# LED_TwoBars.net
KiCad netlist of a schematic drawn in Altium Designer
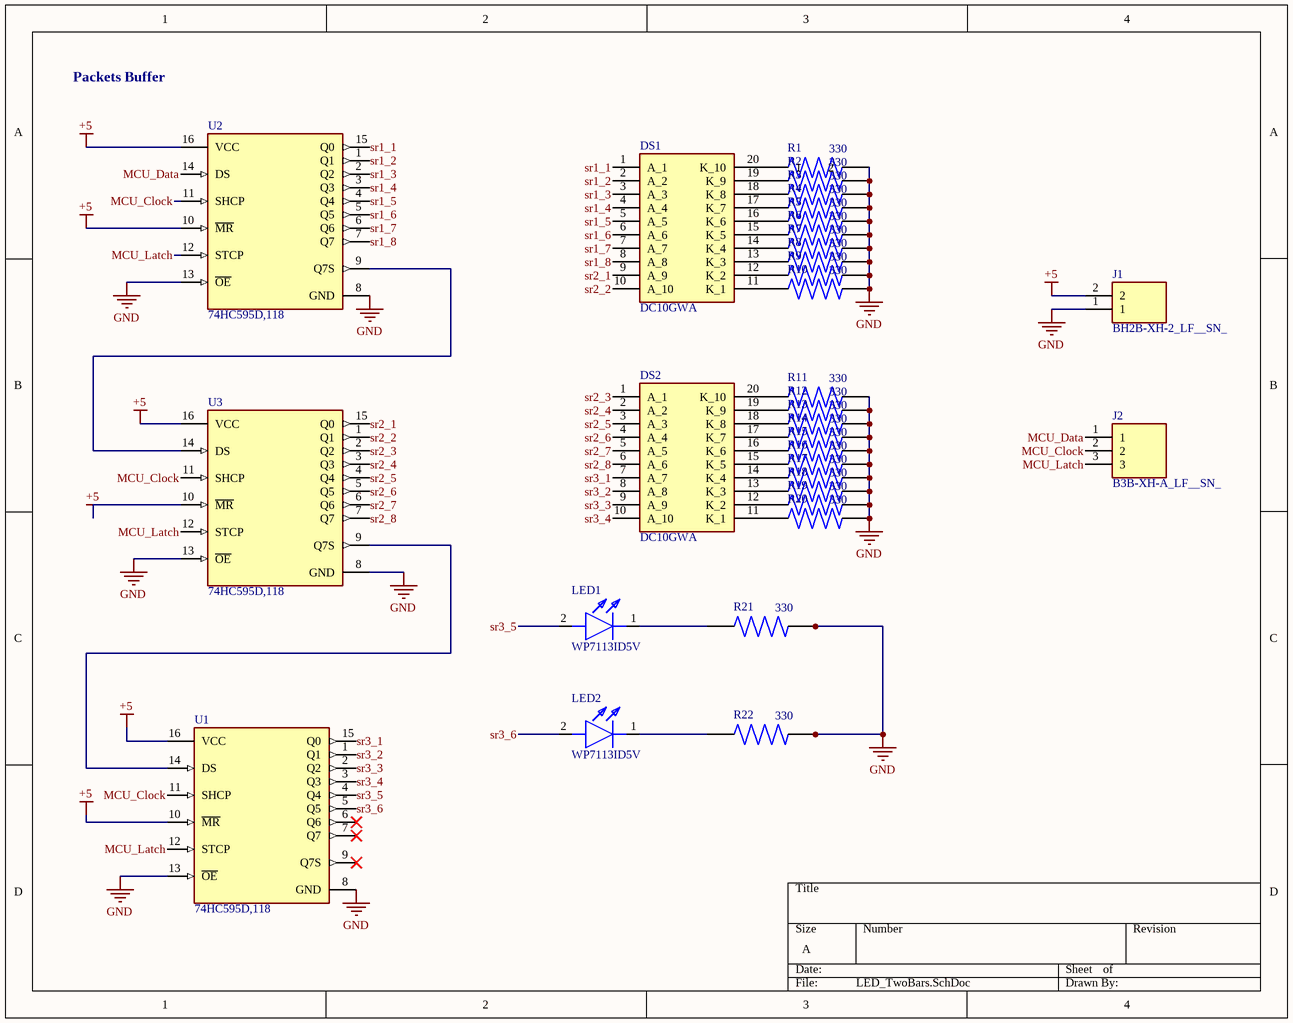
[diagram p0: LED_TwoBars.SchDoc]

(export (version "E")
  (design (tool "Eeschema 10.0.6"))
  (components
    (comp (ref "DS1")
      (value "DC10GWA")
      (footprint "LED_Buffer:DIPS750W75P254L2540H825Q20N")
      (description "Display")
      (fields (field (name "MOUSER PART NUMBER") "604-DC10GWA"))
      (libsource (lib "*") (part "DC10GWA"))
    )
    (comp (ref "DS2")
      (value "DC10GWA")
      (footprint "LED_Buffer:DIPS750W75P254L2540H825Q20N")
      (description "Display")
      (fields (field (name "MOUSER PART NUMBER") "604-DC10GWA"))
      (libsource (lib "*") (part "DC10GWA"))
    )
    (comp (ref "J1")
      (value "BH2B-XH-2_LF__SN_")
      (footprint "LED_Buffer:BH2BXH2LFSN")
      (description "Connector")
      (fields (field (name "MANUFACTURER_PART_NUMBER") "BH2B-XH-2(LF)(SN)"))
      (libsource (lib "LED_Buffer") (part "BH2B-XH-2_LF__SN_"))
    )
    (comp (ref "J2")
      (value "B3B-XH-A_LF__SN_")
      (footprint "LED_Buffer:B3BXHALFSN")
      (description "Connector")
      (fields
        (field (name "MANUFACTURER_PART_NUMBER") "B3B-XH-A(LF)(SN)")
        (field (name "MOUSER PART NUMBER") "306-B3BXHALFSNP")
      )
      (libsource (lib "*") (part "B3B-XH-A_LF__SN_"))
    )
    (comp (ref "LED1")
      (value "WP7113ID5V")
      (footprint "LED_TwoBars:WP7113ID5V")
      (description "LED")
      (fields (field (name "MOUSER PART NUMBER") "604-WP7113ID5V"))
      (libsource (lib "*") (part "WP7113ID5V"))
    )
    (comp (ref "LED2")
      (value "WP7113ID5V")
      (footprint "LED_TwoBars:WP7113ID5V")
      (description "LED")
      (fields (field (name "MOUSER PART NUMBER") "604-WP7113ID5V"))
      (libsource (lib "*") (part "WP7113ID5V"))
    )
    (comp (ref "R1")
      (value "330")
      (footprint "RESC2012X65N")
      (description "330 Ohm 1/8W Thick Film Resistor 0805 Chip - Surface Mount")
      (fields (field (name "MF") "Uni-Royal") (field (name "MP") "0805W8F3300T5E"))
      (libsource (lib "") (part "0805W8F3300T5E_1"))
    )
    (comp (ref "R2")
      (value "330")
      (footprint "RESC2012X65N")
      (description "330 Ohm 1/8W Thick Film Resistor 0805 Chip - Surface Mount")
      (fields (field (name "MF") "Uni-Royal") (field (name "MP") "0805W8F3300T5E"))
      (libsource (lib "Achintha Bandara") (part "0805W8F3300T5E"))
    )
    (comp (ref "R3")
      (value "330")
      (footprint "RESC2012X65N")
      (description "330 Ohm 1/8W Thick Film Resistor 0805 Chip - Surface Mount")
      (fields (field (name "MF") "Uni-Royal") (field (name "MP") "0805W8F3300T5E"))
      (libsource (lib "Achintha Bandara") (part "0805W8F3300T5E"))
    )
    (comp (ref "R4")
      (value "330")
      (footprint "RESC2012X65N")
      (description "330 Ohm 1/8W Thick Film Resistor 0805 Chip - Surface Mount")
      (fields (field (name "MF") "Uni-Royal") (field (name "MP") "0805W8F3300T5E"))
      (libsource (lib "Achintha Bandara") (part "0805W8F3300T5E"))
    )
    (comp (ref "R5")
      (value "330")
      (footprint "RESC2012X65N")
      (description "330 Ohm 1/8W Thick Film Resistor 0805 Chip - Surface Mount")
      (fields (field (name "MF") "Uni-Royal") (field (name "MP") "0805W8F3300T5E"))
      (libsource (lib "Achintha Bandara") (part "0805W8F3300T5E"))
    )
    (comp (ref "R6")
      (value "330")
      (footprint "RESC2012X65N")
      (description "330 Ohm 1/8W Thick Film Resistor 0805 Chip - Surface Mount")
      (fields (field (name "MF") "Uni-Royal") (field (name "MP") "0805W8F3300T5E"))
      (libsource (lib "Achintha Bandara") (part "0805W8F3300T5E"))
    )
    (comp (ref "R7")
      (value "330")
      (footprint "RESC2012X65N")
      (description "330 Ohm 1/8W Thick Film Resistor 0805 Chip - Surface Mount")
      (fields (field (name "MF") "Uni-Royal") (field (name "MP") "0805W8F3300T5E"))
      (libsource (lib "Achintha Bandara") (part "0805W8F3300T5E"))
    )
    (comp (ref "R8")
      (value "330")
      (footprint "RESC2012X65N")
      (description "330 Ohm 1/8W Thick Film Resistor 0805 Chip - Surface Mount")
      (fields (field (name "MF") "Uni-Royal") (field (name "MP") "0805W8F3300T5E"))
      (libsource (lib "Achintha Bandara") (part "0805W8F3300T5E"))
    )
    (comp (ref "R9")
      (value "330")
      (footprint "RESC2012X65N")
      (description "330 Ohm 1/8W Thick Film Resistor 0805 Chip - Surface Mount")
      (fields (field (name "MF") "Uni-Royal") (field (name "MP") "0805W8F3300T5E"))
      (libsource (lib "Achintha Bandara") (part "0805W8F3300T5E"))
    )
    (comp (ref "R10")
      (value "330")
      (footprint "RESC2012X65N")
      (description "330 Ohm 1/8W Thick Film Resistor 0805 Chip - Surface Mount")
      (fields (field (name "MF") "Uni-Royal") (field (name "MP") "0805W8F3300T5E"))
      (libsource (lib "Achintha Bandara") (part "0805W8F3300T5E"))
    )
    (comp (ref "R11")
      (value "330")
      (footprint "RESC2012X65N")
      (description "330 Ohm 1/8W Thick Film Resistor 0805 Chip - Surface Mount")
      (fields (field (name "MF") "Uni-Royal") (field (name "MP") "0805W8F3300T5E"))
      (libsource (lib "Achintha Bandara") (part "0805W8F3300T5E"))
    )
    (comp (ref "R12")
      (value "330")
      (footprint "RESC2012X65N")
      (description "330 Ohm 1/8W Thick Film Resistor 0805 Chip - Surface Mount")
      (fields (field (name "MF") "Uni-Royal") (field (name "MP") "0805W8F3300T5E"))
      (libsource (lib "Achintha Bandara") (part "0805W8F3300T5E"))
    )
    (comp (ref "R13")
      (value "330")
      (footprint "RESC2012X65N")
      (description "330 Ohm 1/8W Thick Film Resistor 0805 Chip - Surface Mount")
      (fields (field (name "MF") "Uni-Royal") (field (name "MP") "0805W8F3300T5E"))
      (libsource (lib "Achintha Bandara") (part "0805W8F3300T5E"))
    )
    (comp (ref "R14")
      (value "330")
      (footprint "RESC2012X65N")
      (description "330 Ohm 1/8W Thick Film Resistor 0805 Chip - Surface Mount")
      (fields (field (name "MF") "Uni-Royal") (field (name "MP") "0805W8F3300T5E"))
      (libsource (lib "Achintha Bandara") (part "0805W8F3300T5E"))
    )
    (comp (ref "R15")
      (value "330")
      (footprint "RESC2012X65N")
      (description "330 Ohm 1/8W Thick Film Resistor 0805 Chip - Surface Mount")
      (fields (field (name "MF") "Uni-Royal") (field (name "MP") "0805W8F3300T5E"))
      (libsource (lib "Achintha Bandara") (part "0805W8F3300T5E"))
    )
    (comp (ref "R16")
      (value "330")
      (footprint "RESC2012X65N")
      (description "330 Ohm 1/8W Thick Film Resistor 0805 Chip - Surface Mount")
      (fields (field (name "MF") "Uni-Royal") (field (name "MP") "0805W8F3300T5E"))
      (libsource (lib "Achintha Bandara") (part "0805W8F3300T5E"))
    )
    (comp (ref "R17")
      (value "330")
      (footprint "RESC2012X65N")
      (description "330 Ohm 1/8W Thick Film Resistor 0805 Chip - Surface Mount")
      (fields (field (name "MF") "Uni-Royal") (field (name "MP") "0805W8F3300T5E"))
      (libsource (lib "Achintha Bandara") (part "0805W8F3300T5E"))
    )
    (comp (ref "R18")
      (value "330")
      (footprint "RESC2012X65N")
      (description "330 Ohm 1/8W Thick Film Resistor 0805 Chip - Surface Mount")
      (fields (field (name "MF") "Uni-Royal") (field (name "MP") "0805W8F3300T5E"))
      (libsource (lib "Achintha Bandara") (part "0805W8F3300T5E"))
    )
    (comp (ref "R19")
      (value "330")
      (footprint "RESC2012X65N")
      (description "330 Ohm 1/8W Thick Film Resistor 0805 Chip - Surface Mount")
      (fields (field (name "MF") "Uni-Royal") (field (name "MP") "0805W8F3300T5E"))
      (libsource (lib "Achintha Bandara") (part "0805W8F3300T5E"))
    )
    (comp (ref "R20")
      (value "330")
      (footprint "RESC2012X65N")
      (description "330 Ohm 1/8W Thick Film Resistor 0805 Chip - Surface Mount")
      (fields (field (name "MF") "Uni-Royal") (field (name "MP") "0805W8F3300T5E"))
      (libsource (lib "Achintha Bandara") (part "0805W8F3300T5E"))
    )
    (comp (ref "R21")
      (value "330")
      (footprint "RESC2012X65N")
      (description "330 Ohm 1/8W Thick Film Resistor 0805 Chip - Surface Mount")
      (fields (field (name "MF") "Uni-Royal") (field (name "MP") "0805W8F3300T5E"))
      (libsource (lib "Achintha Bandara") (part "0805W8F3300T5E"))
    )
    (comp (ref "R22")
      (value "330")
      (footprint "RESC2012X65N")
      (description "330 Ohm 1/8W Thick Film Resistor 0805 Chip - Surface Mount")
      (fields (field (name "MF") "Uni-Royal") (field (name "MP") "0805W8F3300T5E"))
      (libsource (lib "Achintha Bandara") (part "0805W8F3300T5E"))
    )
    (comp (ref "U1")
      (value "74HC595D,118")
      (footprint "FP-SOT109-1-IPC_C")
      (description "IC SHIFT REGISTER 8BIT 16SOIC")
      (libsource (lib "Altium Content Vault") (part "7b153f231cfcc3ac06dee253bd56617"))
    )
    (comp (ref "U2")
      (value "74HC595D,118")
      (footprint "FP-SOT109-1-IPC_C")
      (description "IC SHIFT REGISTER 8BIT 16SOIC")
      (libsource (lib "Altium Content Vault") (part "7b153f231cfcc3ac06dee253bd56617"))
    )
    (comp (ref "U3")
      (value "74HC595D,118")
      (footprint "FP-SOT109-1-IPC_C")
      (description "IC SHIFT REGISTER 8BIT 16SOIC")
      (libsource (lib "Altium Content Vault") (part "7b153f231cfcc3ac06dee253bd56617"))
    )
  )
  (nets
    (net (code "1") (name "+5") (class "Default")
      (node (ref "J1") (pin "2") (pinfunction "2_2") (pintype "passive"))
      (node (ref "U1") (pin "10") (pinfunction "~{MR}_10") (pintype "input"))
      (node (ref "U1") (pin "16") (pinfunction "VCC_16") (pintype "power_in"))
      (node (ref "U2") (pin "10") (pinfunction "~{MR}_10") (pintype "input"))
      (node (ref "U2") (pin "16") (pinfunction "VCC_16") (pintype "power_in"))
      (node (ref "U3") (pin "10") (pinfunction "~{MR}_10") (pintype "input"))
      (node (ref "U3") (pin "16") (pinfunction "VCC_16") (pintype "power_in"))
    )
    (net (code "2") (name "/MCU_Clock") (class "Default")
      (node (ref "J2") (pin "2") (pinfunction "2_2") (pintype "passive"))
      (node (ref "U1") (pin "11") (pinfunction "SHCP_11") (pintype "input"))
      (node (ref "U2") (pin "11") (pinfunction "SHCP_11") (pintype "input"))
      (node (ref "U3") (pin "11") (pinfunction "SHCP_11") (pintype "input"))
    )
    (net (code "3") (name "/MCU_Data") (class "Default")
      (node (ref "J2") (pin "1") (pinfunction "1_1") (pintype "passive"))
      (node (ref "U2") (pin "14") (pinfunction "DS_14") (pintype "input"))
    )
    (net (code "4") (name "/MCU_Latch") (class "Default")
      (node (ref "J2") (pin "3") (pinfunction "3_3") (pintype "passive"))
      (node (ref "U1") (pin "12") (pinfunction "STCP_12") (pintype "input"))
      (node (ref "U2") (pin "12") (pinfunction "STCP_12") (pintype "input"))
      (node (ref "U3") (pin "12") (pinfunction "STCP_12") (pintype "input"))
    )
    (net (code "5") (name "/sr1_1") (class "Default")
      (node (ref "DS1") (pin "1") (pinfunction "A_1_1") (pintype "passive"))
      (node (ref "U2") (pin "15") (pinfunction "Q0_15") (pintype "output"))
    )
    (net (code "6") (name "/sr1_2") (class "Default")
      (node (ref "DS1") (pin "2") (pinfunction "A_2_2") (pintype "passive"))
      (node (ref "U2") (pin "1") (pinfunction "Q1_1") (pintype "output"))
    )
    (net (code "7") (name "/sr1_3") (class "Default")
      (node (ref "DS1") (pin "3") (pinfunction "A_3_3") (pintype "passive"))
      (node (ref "U2") (pin "2") (pinfunction "Q2_2") (pintype "output"))
    )
    (net (code "8") (name "/sr1_4") (class "Default")
      (node (ref "DS1") (pin "4") (pinfunction "A_4_4") (pintype "passive"))
      (node (ref "U2") (pin "3") (pinfunction "Q3_3") (pintype "output"))
    )
    (net (code "9") (name "/sr1_5") (class "Default")
      (node (ref "DS1") (pin "5") (pinfunction "A_5_5") (pintype "passive"))
      (node (ref "U2") (pin "4") (pinfunction "Q4_4") (pintype "output"))
    )
    (net (code "10") (name "/sr1_6") (class "Default")
      (node (ref "DS1") (pin "6") (pinfunction "A_6_6") (pintype "passive"))
      (node (ref "U2") (pin "5") (pinfunction "Q5_5") (pintype "output"))
    )
    (net (code "11") (name "/sr1_7") (class "Default")
      (node (ref "DS1") (pin "7") (pinfunction "A_7_7") (pintype "passive"))
      (node (ref "U2") (pin "6") (pinfunction "Q6_6") (pintype "output"))
    )
    (net (code "12") (name "/sr1_8") (class "Default")
      (node (ref "DS1") (pin "8") (pinfunction "A_8_8") (pintype "passive"))
      (node (ref "U2") (pin "7") (pinfunction "Q7_7") (pintype "output"))
    )
    (net (code "13") (name "/sr2_1") (class "Default")
      (node (ref "DS1") (pin "9") (pinfunction "A_9_9") (pintype "passive"))
      (node (ref "U3") (pin "15") (pinfunction "Q0_15") (pintype "output"))
    )
    (net (code "14") (name "/sr2_2") (class "Default")
      (node (ref "DS1") (pin "10") (pinfunction "A_10_10") (pintype "passive"))
      (node (ref "U3") (pin "1") (pinfunction "Q1_1") (pintype "output"))
    )
    (net (code "15") (name "/sr2_3") (class "Default")
      (node (ref "DS2") (pin "1") (pinfunction "A_1_1") (pintype "passive"))
      (node (ref "U3") (pin "2") (pinfunction "Q2_2") (pintype "output"))
    )
    (net (code "16") (name "/sr2_4") (class "Default")
      (node (ref "DS2") (pin "2") (pinfunction "A_2_2") (pintype "passive"))
      (node (ref "U3") (pin "3") (pinfunction "Q3_3") (pintype "output"))
    )
    (net (code "17") (name "/sr2_5") (class "Default")
      (node (ref "DS2") (pin "3") (pinfunction "A_3_3") (pintype "passive"))
      (node (ref "U3") (pin "4") (pinfunction "Q4_4") (pintype "output"))
    )
    (net (code "18") (name "/sr2_6") (class "Default")
      (node (ref "DS2") (pin "4") (pinfunction "A_4_4") (pintype "passive"))
      (node (ref "U3") (pin "5") (pinfunction "Q5_5") (pintype "output"))
    )
    (net (code "19") (name "/sr2_7") (class "Default")
      (node (ref "DS2") (pin "5") (pinfunction "A_5_5") (pintype "passive"))
      (node (ref "U3") (pin "6") (pinfunction "Q6_6") (pintype "output"))
    )
    (net (code "20") (name "/sr2_8") (class "Default")
      (node (ref "DS2") (pin "6") (pinfunction "A_6_6") (pintype "passive"))
      (node (ref "U3") (pin "7") (pinfunction "Q7_7") (pintype "output"))
    )
    (net (code "21") (name "/sr3_1") (class "Default")
      (node (ref "DS2") (pin "7") (pinfunction "A_7_7") (pintype "passive"))
      (node (ref "U1") (pin "15") (pinfunction "Q0_15") (pintype "output"))
    )
    (net (code "22") (name "/sr3_2") (class "Default")
      (node (ref "DS2") (pin "8") (pinfunction "A_8_8") (pintype "passive"))
      (node (ref "U1") (pin "1") (pinfunction "Q1_1") (pintype "output"))
    )
    (net (code "23") (name "/sr3_3") (class "Default")
      (node (ref "DS2") (pin "9") (pinfunction "A_9_9") (pintype "passive"))
      (node (ref "U1") (pin "2") (pinfunction "Q2_2") (pintype "output"))
    )
    (net (code "24") (name "/sr3_4") (class "Default")
      (node (ref "DS2") (pin "10") (pinfunction "A_10_10") (pintype "passive"))
      (node (ref "U1") (pin "3") (pinfunction "Q3_3") (pintype "output"))
    )
    (net (code "25") (name "/sr3_5") (class "Default")
      (node (ref "LED1") (pin "2") (pinfunction "A_2") (pintype "passive"))
      (node (ref "U1") (pin "4") (pinfunction "Q4_4") (pintype "output"))
    )
    (net (code "26") (name "/sr3_6") (class "Default")
      (node (ref "LED2") (pin "2") (pinfunction "A_2") (pintype "passive"))
      (node (ref "U1") (pin "5") (pinfunction "Q5_5") (pintype "output"))
    )
    (net (code "27") (name "GND") (class "Default")
      (node (ref "J1") (pin "1") (pinfunction "1_1") (pintype "passive"))
      (node (ref "R1") (pin "2") (pinfunction "2_2") (pintype "passive"))
      (node (ref "R10") (pin "2") (pinfunction "2_2") (pintype "passive"))
      (node (ref "R11") (pin "2") (pinfunction "2_2") (pintype "passive"))
      (node (ref "R12") (pin "2") (pinfunction "2_2") (pintype "passive"))
      (node (ref "R13") (pin "2") (pinfunction "2_2") (pintype "passive"))
      (node (ref "R14") (pin "2") (pinfunction "2_2") (pintype "passive"))
      (node (ref "R15") (pin "2") (pinfunction "2_2") (pintype "passive"))
      (node (ref "R16") (pin "2") (pinfunction "2_2") (pintype "passive"))
      (node (ref "R17") (pin "2") (pinfunction "2_2") (pintype "passive"))
      (node (ref "R18") (pin "2") (pinfunction "2_2") (pintype "passive"))
      (node (ref "R19") (pin "2") (pinfunction "2_2") (pintype "passive"))
      (node (ref "R2") (pin "2") (pinfunction "2_2") (pintype "passive"))
      (node (ref "R20") (pin "2") (pinfunction "2_2") (pintype "passive"))
      (node (ref "R21") (pin "2") (pinfunction "2_2") (pintype "passive"))
      (node (ref "R22") (pin "2") (pinfunction "2_2") (pintype "passive"))
      (node (ref "R3") (pin "2") (pinfunction "2_2") (pintype "passive"))
      (node (ref "R4") (pin "2") (pinfunction "2_2") (pintype "passive"))
      (node (ref "R5") (pin "2") (pinfunction "2_2") (pintype "passive"))
      (node (ref "R6") (pin "2") (pinfunction "2_2") (pintype "passive"))
      (node (ref "R7") (pin "2") (pinfunction "2_2") (pintype "passive"))
      (node (ref "R8") (pin "2") (pinfunction "2_2") (pintype "passive"))
      (node (ref "R9") (pin "2") (pinfunction "2_2") (pintype "passive"))
      (node (ref "U1") (pin "13") (pinfunction "~{OE}_13") (pintype "input"))
      (node (ref "U1") (pin "8") (pinfunction "GND_8") (pintype "power_in"))
      (node (ref "U2") (pin "13") (pinfunction "~{OE}_13") (pintype "input"))
      (node (ref "U2") (pin "8") (pinfunction "GND_8") (pintype "power_in"))
      (node (ref "U3") (pin "13") (pinfunction "~{OE}_13") (pintype "input"))
      (node (ref "U3") (pin "8") (pinfunction "GND_8") (pintype "power_in"))
    )
    (net (code "28") (name "Net-(DS1-K_1)") (class "Default")
      (node (ref "DS1") (pin "11") (pinfunction "K_1_11") (pintype "passive"))
      (node (ref "R10") (pin "1") (pinfunction "1_1") (pintype "passive"))
    )
    (net (code "29") (name "Net-(DS1-K_2)") (class "Default")
      (node (ref "DS1") (pin "12") (pinfunction "K_2_12") (pintype "passive"))
      (node (ref "R9") (pin "1") (pinfunction "1_1") (pintype "passive"))
    )
    (net (code "30") (name "Net-(DS1-K_3)") (class "Default")
      (node (ref "DS1") (pin "13") (pinfunction "K_3_13") (pintype "passive"))
      (node (ref "R8") (pin "1") (pinfunction "1_1") (pintype "passive"))
    )
    (net (code "31") (name "Net-(DS1-K_4)") (class "Default")
      (node (ref "DS1") (pin "14") (pinfunction "K_4_14") (pintype "passive"))
      (node (ref "R7") (pin "1") (pinfunction "1_1") (pintype "passive"))
    )
    (net (code "32") (name "Net-(DS1-K_5)") (class "Default")
      (node (ref "DS1") (pin "15") (pinfunction "K_5_15") (pintype "passive"))
      (node (ref "R6") (pin "1") (pinfunction "1_1") (pintype "passive"))
    )
    (net (code "33") (name "Net-(DS1-K_6)") (class "Default")
      (node (ref "DS1") (pin "16") (pinfunction "K_6_16") (pintype "passive"))
      (node (ref "R5") (pin "1") (pinfunction "1_1") (pintype "passive"))
    )
    (net (code "34") (name "Net-(DS1-K_7)") (class "Default")
      (node (ref "DS1") (pin "17") (pinfunction "K_7_17") (pintype "passive"))
      (node (ref "R4") (pin "1") (pinfunction "1_1") (pintype "passive"))
    )
    (net (code "35") (name "Net-(DS1-K_8)") (class "Default")
      (node (ref "DS1") (pin "18") (pinfunction "K_8_18") (pintype "passive"))
      (node (ref "R3") (pin "1") (pinfunction "1_1") (pintype "passive"))
    )
    (net (code "36") (name "Net-(DS1-K_9)") (class "Default")
      (node (ref "DS1") (pin "19") (pinfunction "K_9_19") (pintype "passive"))
      (node (ref "R2") (pin "1") (pinfunction "1_1") (pintype "passive"))
    )
    (net (code "37") (name "Net-(DS1-K_10)") (class "Default")
      (node (ref "DS1") (pin "20") (pinfunction "K_10_20") (pintype "passive"))
      (node (ref "R1") (pin "1") (pinfunction "1_1") (pintype "passive"))
    )
    (net (code "38") (name "Net-(DS2-K_1)") (class "Default")
      (node (ref "DS2") (pin "11") (pinfunction "K_1_11") (pintype "passive"))
      (node (ref "R20") (pin "1") (pinfunction "1_1") (pintype "passive"))
    )
    (net (code "39") (name "Net-(DS2-K_2)") (class "Default")
      (node (ref "DS2") (pin "12") (pinfunction "K_2_12") (pintype "passive"))
      (node (ref "R19") (pin "1") (pinfunction "1_1") (pintype "passive"))
    )
    (net (code "40") (name "Net-(DS2-K_3)") (class "Default")
      (node (ref "DS2") (pin "13") (pinfunction "K_3_13") (pintype "passive"))
      (node (ref "R18") (pin "1") (pinfunction "1_1") (pintype "passive"))
    )
    (net (code "41") (name "Net-(DS2-K_4)") (class "Default")
      (node (ref "DS2") (pin "14") (pinfunction "K_4_14") (pintype "passive"))
      (node (ref "R17") (pin "1") (pinfunction "1_1") (pintype "passive"))
    )
    (net (code "42") (name "Net-(DS2-K_5)") (class "Default")
      (node (ref "DS2") (pin "15") (pinfunction "K_5_15") (pintype "passive"))
      (node (ref "R16") (pin "1") (pinfunction "1_1") (pintype "passive"))
    )
    (net (code "43") (name "Net-(DS2-K_6)") (class "Default")
      (node (ref "DS2") (pin "16") (pinfunction "K_6_16") (pintype "passive"))
      (node (ref "R15") (pin "1") (pinfunction "1_1") (pintype "passive"))
    )
    (net (code "44") (name "Net-(DS2-K_7)") (class "Default")
      (node (ref "DS2") (pin "17") (pinfunction "K_7_17") (pintype "passive"))
      (node (ref "R14") (pin "1") (pinfunction "1_1") (pintype "passive"))
    )
    (net (code "45") (name "Net-(DS2-K_8)") (class "Default")
      (node (ref "DS2") (pin "18") (pinfunction "K_8_18") (pintype "passive"))
      (node (ref "R13") (pin "1") (pinfunction "1_1") (pintype "passive"))
    )
    (net (code "46") (name "Net-(DS2-K_9)") (class "Default")
      (node (ref "DS2") (pin "19") (pinfunction "K_9_19") (pintype "passive"))
      (node (ref "R12") (pin "1") (pinfunction "1_1") (pintype "passive"))
    )
    (net (code "47") (name "Net-(DS2-K_10)") (class "Default")
      (node (ref "DS2") (pin "20") (pinfunction "K_10_20") (pintype "passive"))
      (node (ref "R11") (pin "1") (pinfunction "1_1") (pintype "passive"))
    )
    (net (code "48") (name "Net-(LED1-K)") (class "Default")
      (node (ref "LED1") (pin "1") (pinfunction "K_1") (pintype "passive"))
      (node (ref "R21") (pin "1") (pinfunction "1_1") (pintype "passive"))
    )
    (net (code "49") (name "Net-(LED2-K)") (class "Default")
      (node (ref "LED2") (pin "1") (pinfunction "K_1") (pintype "passive"))
      (node (ref "R22") (pin "1") (pinfunction "1_1") (pintype "passive"))
    )
    (net (code "50") (name "Net-(U1-DS)") (class "Default")
      (node (ref "U1") (pin "14") (pinfunction "DS_14") (pintype "input"))
      (node (ref "U3") (pin "9") (pinfunction "Q7S_9") (pintype "output"))
    )
    (net (code "51") (name "Net-(U2-Q7S)") (class "Default")
      (node (ref "U2") (pin "9") (pinfunction "Q7S_9") (pintype "output"))
      (node (ref "U3") (pin "14") (pinfunction "DS_14") (pintype "input"))
    )
    (net (code "52") (name "unconnected-(U1-Q6-Pad6)") (class "Default")
      (node (ref "U1") (pin "6") (pinfunction "Q6_6") (pintype "output+no_connect"))
    )
    (net (code "53") (name "unconnected-(U1-Q7-Pad7)") (class "Default")
      (node (ref "U1") (pin "7") (pinfunction "Q7_7") (pintype "output+no_connect"))
    )
    (net (code "54") (name "unconnected-(U1-Q7S-Pad9)") (class "Default")
      (node (ref "U1") (pin "9") (pinfunction "Q7S_9") (pintype "output+no_connect"))
    )
  )
)
